# SCH_Line_Follower_Robot_Jao.net
KiCad netlist of a schematic drawn in EasyEDA
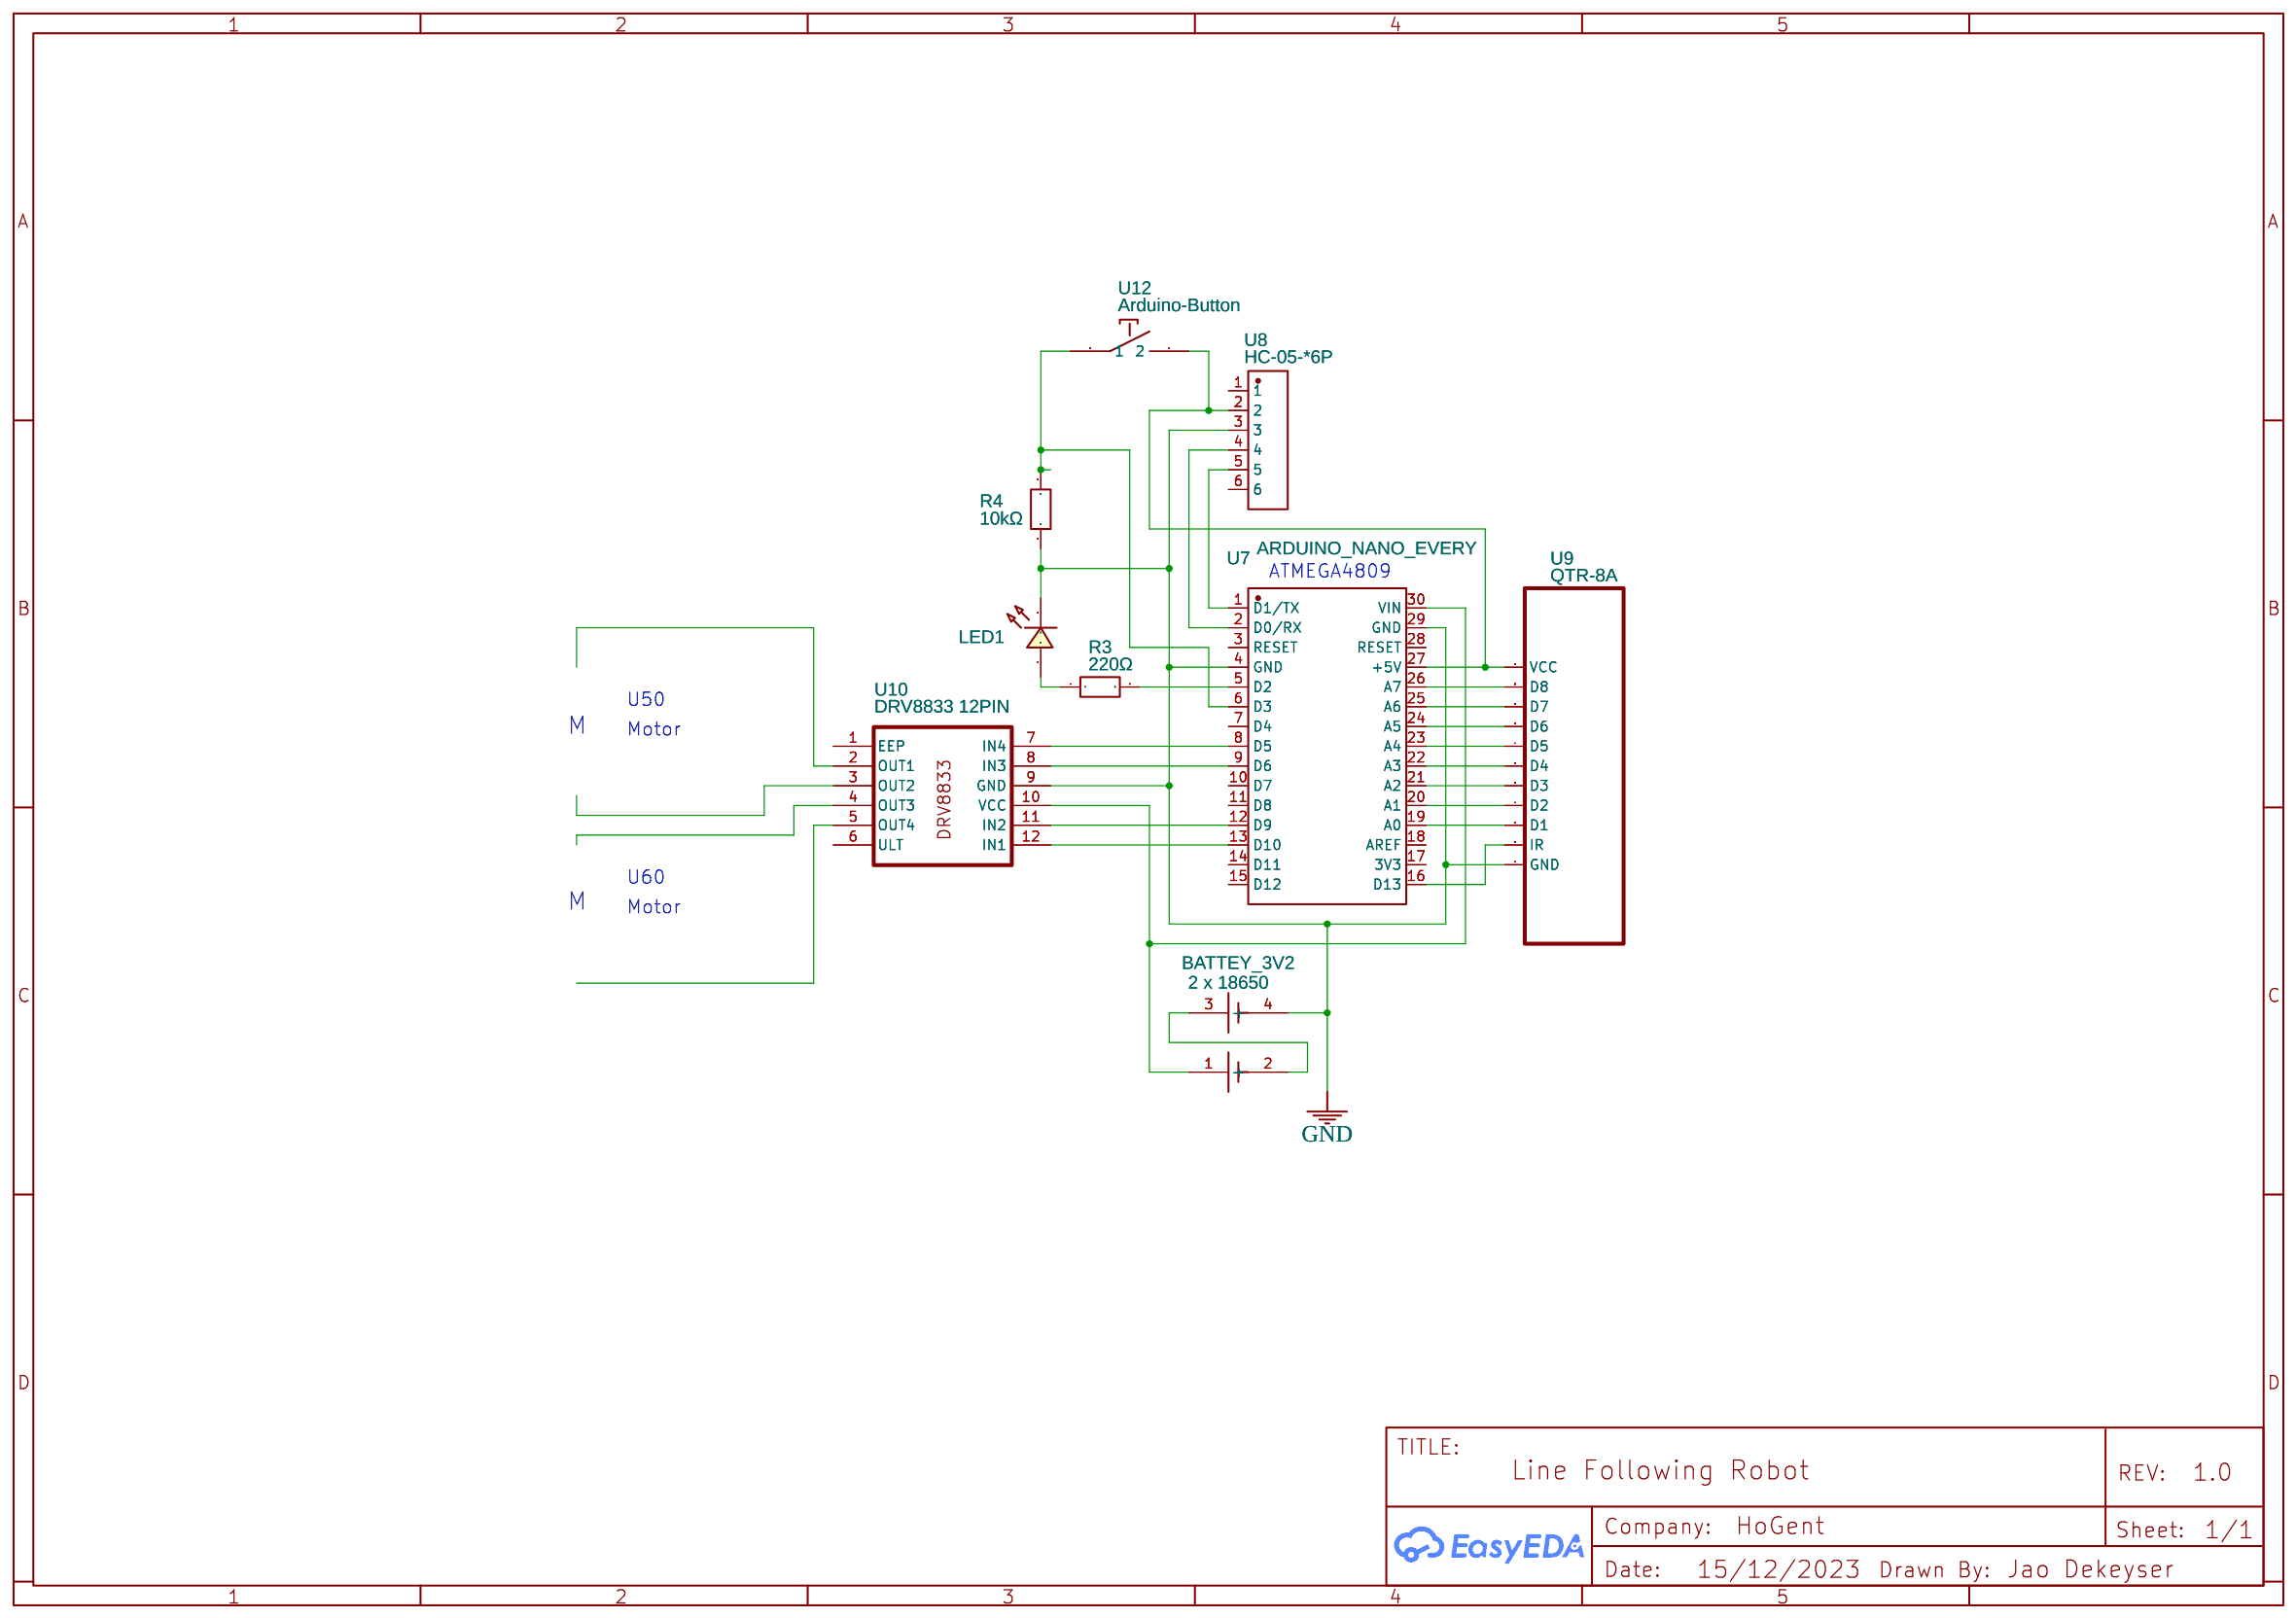
[diagram p0: schematic sheet]

(export (version "E")
  (design (tool "Eeschema 10.0.6"))
  (components
    (comp (ref "BATTEY_3V2")
      (value "2 x 18650")
      (fields (field (name "Manufacturer Part") "BAT_X2_18650") (field (name "Manufacturer") "Dex"))
      (libsource (lib "") (part "BAT_X2_18650"))
    )
    (comp (ref "LED1")
      (value "LED-TH-5mm_R")
      (fields
        (field (name "Manufacturer Part") "333-2SURD/S530-A3")
        (field (name "Manufacturer") "EVERLIGHT(台湾亿光)")
      )
      (libsource (lib "") (part "LED-TH-5mm_R"))
    )
    (comp (ref "R3")
      (value "220Ω")
      (libsource (lib "") (part "AXIAL RESISTOR 220 OHM - TH_BD2.3-L6.0-P10.00-D0.4_1"))
    )
    (comp (ref "R4")
      (value "10kΩ")
      (libsource (lib "") (part "AXIAL RESISTOR 220 OHM - TH_BD2.3-L6.0-P10.00-D0.4"))
    )
    (comp (ref "U7")
      (value "ARDUINO_NANO_EVERY")
      (fields (field (name "Manufacturer Part") "ARDUINO_NANO"))
      (libsource (lib "") (part "ARDUINO_NANO"))
    )
    (comp (ref "U8")
      (value "HC-05-*6P")
      (fields (field (name "Manufacturer Part") "HC-05_排母*6P"))
      (libsource (lib "") (part "HC-05-*6P"))
    )
    (comp (ref "U9") (value "QTR-8A") (libsource (lib "") (part "QTR-8A")))
    (comp (ref "U10") (value "DRV8833 12PIN") (libsource (lib "") (part "DRV8833 12PIN")))
    (comp (ref "U12")
      (value "Arduino-Button")
      (fields (field (name "Manufacturer Part") "SW100664"))
      (libsource (lib "") (part "Arduino-Button"))
    )
  )
  (nets
    (net (code "1") (name "GND") (class "Default")
      (node (ref "BATTEY_3V2") (pin "4") (pinfunction "-_4") (pintype "unspecified"))
      (node (ref "LED1") (pin "2") (pinfunction "2_2") (pintype "unspecified"))
      (node (ref "R4") (pin "1") (pinfunction "1_1") (pintype "unspecified"))
      (node (ref "U10") (pin "9") (pinfunction "GND_9") (pintype "unspecified"))
      (node (ref "U7") (pin "29") (pinfunction "GND_29") (pintype "unspecified"))
      (node (ref "U7") (pin "4") (pinfunction "GND_4") (pintype "unspecified"))
      (node (ref "U8") (pin "3") (pinfunction "3_3") (pintype "unspecified"))
      (node (ref "U9") (pin "1") (pinfunction "GND_1") (pintype "unspecified"))
    )
    (net (code "2") (name "Net-(BATTEY_3V2-+-Pad3)") (class "Default")
      (node (ref "BATTEY_3V2") (pin "2") (pinfunction "-_2") (pintype "unspecified"))
      (node (ref "BATTEY_3V2") (pin "3") (pinfunction "+_3") (pintype "unspecified"))
    )
    (net (code "3") (name "Net-(LED1-Pad1)") (class "Default")
      (node (ref "LED1") (pin "1") (pinfunction "1_1") (pintype "unspecified"))
      (node (ref "R3") (pin "1") (pinfunction "1_1") (pintype "unspecified"))
    )
    (net (code "4") (name "Net-(U7-+5V)") (class "Default")
      (node (ref "U12") (pin "2") (pinfunction "2_2") (pintype "unspecified"))
      (node (ref "U7") (pin "27") (pinfunction "+5V_27") (pintype "unspecified"))
      (node (ref "U8") (pin "2") (pinfunction "2_2") (pintype "unspecified"))
      (node (ref "U9") (pin "11") (pinfunction "VCC_11") (pintype "unspecified"))
    )
    (net (code "5") (name "Net-(U7-A0)") (class "Default")
      (node (ref "U7") (pin "19") (pinfunction "A0_19") (pintype "unspecified"))
      (node (ref "U9") (pin "3") (pinfunction "D1_3") (pintype "unspecified"))
    )
    (net (code "6") (name "Net-(U7-A1)") (class "Default")
      (node (ref "U7") (pin "20") (pinfunction "A1_20") (pintype "unspecified"))
      (node (ref "U9") (pin "4") (pinfunction "D2_4") (pintype "unspecified"))
    )
    (net (code "7") (name "Net-(U7-A2)") (class "Default")
      (node (ref "U7") (pin "21") (pinfunction "A2_21") (pintype "unspecified"))
      (node (ref "U9") (pin "5") (pinfunction "D3_5") (pintype "unspecified"))
    )
    (net (code "8") (name "Net-(U7-A3)") (class "Default")
      (node (ref "U7") (pin "22") (pinfunction "A3_22") (pintype "unspecified"))
      (node (ref "U9") (pin "6") (pinfunction "D4_6") (pintype "unspecified"))
    )
    (net (code "9") (name "Net-(U7-A4)") (class "Default")
      (node (ref "U7") (pin "23") (pinfunction "A4_23") (pintype "unspecified"))
      (node (ref "U9") (pin "7") (pinfunction "D5_7") (pintype "unspecified"))
    )
    (net (code "10") (name "Net-(U7-A5)") (class "Default")
      (node (ref "U7") (pin "24") (pinfunction "A5_24") (pintype "unspecified"))
      (node (ref "U9") (pin "8") (pinfunction "D6_8") (pintype "unspecified"))
    )
    (net (code "11") (name "Net-(U7-A6)") (class "Default")
      (node (ref "U7") (pin "25") (pinfunction "A6_25") (pintype "unspecified"))
      (node (ref "U9") (pin "9") (pinfunction "D7_9") (pintype "unspecified"))
    )
    (net (code "12") (name "Net-(U7-A7)") (class "Default")
      (node (ref "U7") (pin "26") (pinfunction "A7_26") (pintype "unspecified"))
      (node (ref "U9") (pin "10") (pinfunction "D8_10") (pintype "unspecified"))
    )
    (net (code "13") (name "Net-(U7-D0{slash}RX)") (class "Default")
      (node (ref "U7") (pin "2") (pinfunction "D0/RX_2") (pintype "unspecified"))
      (node (ref "U8") (pin "4") (pinfunction "4_4") (pintype "unspecified"))
    )
    (net (code "14") (name "Net-(U7-D1{slash}TX)") (class "Default")
      (node (ref "U7") (pin "1") (pinfunction "D1/TX_1") (pintype "unspecified"))
      (node (ref "U8") (pin "5") (pinfunction "5_5") (pintype "unspecified"))
    )
    (net (code "15") (name "Net-(U7-D2)") (class "Default")
      (node (ref "R3") (pin "2") (pinfunction "2_2") (pintype "unspecified"))
      (node (ref "U7") (pin "5") (pinfunction "D2_5") (pintype "unspecified"))
    )
    (net (code "16") (name "Net-(U7-D3)") (class "Default")
      (node (ref "R4") (pin "2") (pinfunction "2_2") (pintype "unspecified"))
      (node (ref "U12") (pin "1") (pinfunction "1_1") (pintype "unspecified"))
      (node (ref "U7") (pin "6") (pinfunction "D3_6") (pintype "unspecified"))
    )
    (net (code "17") (name "Net-(U7-D13)") (class "Default")
      (node (ref "U7") (pin "16") (pinfunction "D13_16") (pintype "unspecified"))
      (node (ref "U9") (pin "2") (pinfunction "IR_2") (pintype "unspecified"))
    )
    (net (code "18") (name "Net-(U10-IN1)") (class "Default")
      (node (ref "U10") (pin "12") (pinfunction "IN1_12") (pintype "unspecified"))
      (node (ref "U7") (pin "13") (pinfunction "D10_13") (pintype "unspecified"))
    )
    (net (code "19") (name "Net-(U10-IN2)") (class "Default")
      (node (ref "U10") (pin "11") (pinfunction "IN2_11") (pintype "unspecified"))
      (node (ref "U7") (pin "12") (pinfunction "D9_12") (pintype "unspecified"))
    )
    (net (code "20") (name "Net-(U10-IN3)") (class "Default")
      (node (ref "U10") (pin "8") (pinfunction "IN3_8") (pintype "unspecified"))
      (node (ref "U7") (pin "9") (pinfunction "D6_9") (pintype "unspecified"))
    )
    (net (code "21") (name "Net-(U10-IN4)") (class "Default")
      (node (ref "U10") (pin "7") (pinfunction "IN4_7") (pintype "unspecified"))
      (node (ref "U7") (pin "8") (pinfunction "D5_8") (pintype "unspecified"))
    )
    (net (code "22") (name "Net-(U10-VCC)") (class "Default")
      (node (ref "BATTEY_3V2") (pin "1") (pinfunction "+_1") (pintype "unspecified"))
      (node (ref "U10") (pin "10") (pinfunction "VCC_10") (pintype "unspecified"))
      (node (ref "U7") (pin "30") (pinfunction "VIN_30") (pintype "unspecified"))
    )
    (net (code "23") (name "unconnected-(U7-3V3-Pad17)") (class "Default")
      (node (ref "U7") (pin "17") (pinfunction "3V3_17") (pintype "unspecified"))
    )
    (net (code "24") (name "unconnected-(U7-AREF-Pad18)") (class "Default")
      (node (ref "U7") (pin "18") (pinfunction "AREF_18") (pintype "unspecified"))
    )
    (net (code "25") (name "unconnected-(U7-D4-Pad7)") (class "Default")
      (node (ref "U7") (pin "7") (pinfunction "D4_7") (pintype "unspecified"))
    )
    (net (code "26") (name "unconnected-(U7-D7-Pad10)") (class "Default")
      (node (ref "U7") (pin "10") (pinfunction "D7_10") (pintype "unspecified"))
    )
    (net (code "27") (name "unconnected-(U7-D8-Pad11)") (class "Default")
      (node (ref "U7") (pin "11") (pinfunction "D8_11") (pintype "unspecified"))
    )
    (net (code "28") (name "unconnected-(U7-D11-Pad14)") (class "Default")
      (node (ref "U7") (pin "14") (pinfunction "D11_14") (pintype "unspecified"))
    )
    (net (code "29") (name "unconnected-(U7-D12-Pad15)") (class "Default")
      (node (ref "U7") (pin "15") (pinfunction "D12_15") (pintype "unspecified"))
    )
    (net (code "30") (name "unconnected-(U7-RESET-Pad3)") (class "Default")
      (node (ref "U7") (pin "3") (pinfunction "RESET_3") (pintype "unspecified"))
    )
    (net (code "31") (name "unconnected-(U7-RESET-Pad28)") (class "Default")
      (node (ref "U7") (pin "28") (pinfunction "RESET_28") (pintype "unspecified"))
    )
    (net (code "32") (name "unconnected-(U8-Pad1)") (class "Default")
      (node (ref "U8") (pin "1") (pinfunction "1_1") (pintype "unspecified"))
    )
    (net (code "33") (name "unconnected-(U8-Pad6)") (class "Default")
      (node (ref "U8") (pin "6") (pinfunction "6_6") (pintype "unspecified"))
    )
    (net (code "34") (name "unconnected-(U10-EEP-Pad1)") (class "Default")
      (node (ref "U10") (pin "1") (pinfunction "EEP_1") (pintype "unspecified"))
    )
    (net (code "35") (name "unconnected-(U10-OUT1-Pad2)") (class "Default")
      (node (ref "U10") (pin "2") (pinfunction "OUT1_2") (pintype "unspecified"))
    )
    (net (code "36") (name "unconnected-(U10-OUT2-Pad3)") (class "Default")
      (node (ref "U10") (pin "3") (pinfunction "OUT2_3") (pintype "unspecified"))
    )
    (net (code "37") (name "unconnected-(U10-OUT3-Pad4)") (class "Default")
      (node (ref "U10") (pin "4") (pinfunction "OUT3_4") (pintype "unspecified"))
    )
    (net (code "38") (name "unconnected-(U10-OUT4-Pad5)") (class "Default")
      (node (ref "U10") (pin "5") (pinfunction "OUT4_5") (pintype "unspecified"))
    )
    (net (code "39") (name "unconnected-(U10-ULT-Pad6)") (class "Default")
      (node (ref "U10") (pin "6") (pinfunction "ULT_6") (pintype "unspecified"))
    )
  )
)
